# SensorBoard.net
KiCad netlist of a schematic drawn in EAGLE
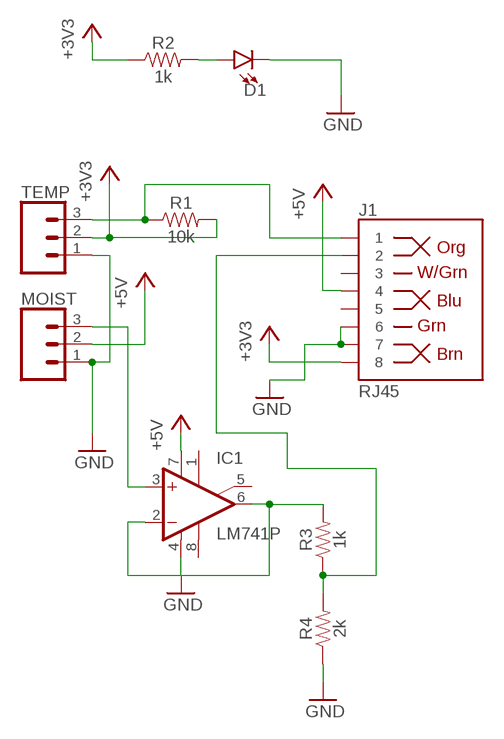
[diagram p0: schematic, sheet 1]

(export (version "E")
  (design (tool "Eeschema 10.0.6"))
  (components
    (comp (ref "D1")
      (value "LED3MM")
      (footprint "eagle-import:LED_3MM")
      (libsource (lib "eagle-import") (part "LED3MM"))
    )
    (comp (ref "IC1")
      (value "LM741P")
      (footprint "eagle-import:DIL08")
      (libsource (lib "eagle-import") (part "741PLM"))
    )
    (comp (ref "J1")
      (value "RJ45")
      (footprint "eagle-import:RJ45-8")
      (libsource (lib "eagle-import") (part "RJ45-8"))
    )
    (comp (ref "MOIST")
      (value "CONN_03")
      (footprint "eagle-import:1X03")
      (libsource (lib "eagle-import") (part "CONN_03"))
    )
    (comp (ref "R1")
      (value "10k")
      (footprint "eagle-import:AXIAL-0.3")
      (libsource (lib "eagle-import") (part "1KOHM-HORIZ-1/4W-1%"))
    )
    (comp (ref "R2")
      (value "1k")
      (footprint "eagle-import:AXIAL-0.3")
      (libsource (lib "eagle-import") (part "1KOHM-HORIZ-1/4W-1%"))
    )
    (comp (ref "R3")
      (value "1k")
      (footprint "eagle-import:AXIAL-0.3")
      (libsource (lib "eagle-import") (part "1KOHM-HORIZ-1/4W-1%"))
    )
    (comp (ref "R4")
      (value "2k")
      (footprint "eagle-import:AXIAL-0.3")
      (libsource (lib "eagle-import") (part "1KOHM-HORIZ-1/4W-1%"))
    )
    (comp (ref "TEMP")
      (value "CONN_03")
      (footprint "eagle-import:1X03")
      (libsource (lib "eagle-import") (part "CONN_03"))
    )
  )
  (nets
    (net (code "1") (name "+3V3") (class "Default")
      (node (ref "J1") (pin "8") (pinfunction "8_8") (pintype "bidirectional"))
      (node (ref "R1") (pin "P$2") (pinfunction "2_P$2") (pintype "passive"))
      (node (ref "R2") (pin "P$1") (pinfunction "1_P$1") (pintype "passive"))
      (node (ref "TEMP") (pin "2") (pinfunction "2_2") (pintype "passive"))
    )
    (net (code "2") (name "+5V") (class "Default")
      (node (ref "IC1") (pin "7") (pinfunction "V+_7") (pintype "power_in"))
      (node (ref "J1") (pin "4") (pinfunction "4_4") (pintype "bidirectional"))
      (node (ref "MOIST") (pin "2") (pinfunction "2_2") (pintype "passive"))
    )
    (net (code "3") (name "GND") (class "Default")
      (node (ref "D1") (pin "K") (pinfunction "C_K") (pintype "passive"))
      (node (ref "IC1") (pin "4") (pinfunction "V-_4") (pintype "power_in"))
      (node (ref "J1") (pin "6") (pinfunction "6_6") (pintype "bidirectional"))
      (node (ref "J1") (pin "7") (pinfunction "7_7") (pintype "bidirectional"))
      (node (ref "MOIST") (pin "1") (pinfunction "1_1") (pintype "passive"))
      (node (ref "R4") (pin "P$1") (pinfunction "1_P$1") (pintype "passive"))
      (node (ref "TEMP") (pin "1") (pinfunction "1_1") (pintype "passive"))
    )
    (net (code "4") (name "Net-(IC1-+IN)") (class "Default")
      (node (ref "IC1") (pin "3") (pinfunction "+IN_3") (pintype "input"))
      (node (ref "MOIST") (pin "3") (pinfunction "3_3") (pintype "passive"))
    )
    (net (code "5") (name "Net-(IC1--IN)") (class "Default")
      (node (ref "IC1") (pin "2") (pinfunction "-IN_2") (pintype "input"))
      (node (ref "IC1") (pin "6") (pinfunction "OUT_6") (pintype "output"))
      (node (ref "R3") (pin "P$2") (pinfunction "2_P$2") (pintype "passive"))
    )
    (net (code "6") (name "Net-(R1-1)") (class "Default")
      (node (ref "J1") (pin "1") (pinfunction "1_1") (pintype "bidirectional"))
      (node (ref "R1") (pin "P$1") (pinfunction "1_P$1") (pintype "passive"))
      (node (ref "TEMP") (pin "3") (pinfunction "3_3") (pintype "passive"))
    )
    (net (code "7") (name "Net-(R2-2)") (class "Default")
      (node (ref "D1") (pin "A") (pinfunction "A_A") (pintype "passive"))
      (node (ref "R2") (pin "P$2") (pinfunction "2_P$2") (pintype "passive"))
    )
    (net (code "8") (name "Net-(R3-1)") (class "Default")
      (node (ref "J1") (pin "2") (pinfunction "2_2") (pintype "bidirectional"))
      (node (ref "R3") (pin "P$1") (pinfunction "1_P$1") (pintype "passive"))
      (node (ref "R4") (pin "P$2") (pinfunction "2_P$2") (pintype "passive"))
    )
    (net (code "9") (name "unconnected-(IC1-ON1-Pad1)") (class "Default")
      (node (ref "IC1") (pin "1") (pinfunction "ON1_1") (pintype "passive"))
    )
    (net (code "10") (name "unconnected-(IC1-ON2-Pad5)") (class "Default")
      (node (ref "IC1") (pin "5") (pinfunction "ON2_5") (pintype "passive"))
    )
    (net (code "11") (name "unconnected-(IC1-OPT-Pad8)") (class "Default")
      (node (ref "IC1") (pin "8") (pinfunction "OPT_8") (pintype "passive"))
    )
    (net (code "12") (name "unconnected-(J1-Pad3)") (class "Default")
      (node (ref "J1") (pin "3") (pinfunction "3_3") (pintype "bidirectional"))
    )
    (net (code "13") (name "unconnected-(J1-Pad5)") (class "Default")
      (node (ref "J1") (pin "5") (pinfunction "5_5") (pintype "bidirectional"))
    )
  )
)
